# TwoPinSherlockDistribution.net
KiCad netlist of a schematic drawn in Altium Designer
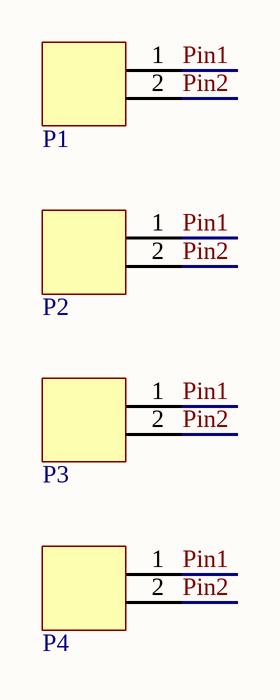
[diagram p0: TwoPinSherlockDistribution.SchDoc]

(export (version "E")
  (design (tool "Eeschema 10.0.6"))
  (components
    (comp (ref "P1")
      (value "2-pin Horz Sherlock")
      (footprint "MOLEX-HDR-1X2-SHERLOCK-HORZ")
      (fields
        (field (name "MANUFACTURER PART NUMBER") "0353630260")
        (field (name "MANUFACTURER") "Molex Inc")
      )
      (libsource (lib "SubjuGator8") (part "MOLEX-HDR-1x2-SHERLOCK_RA"))
    )
    (comp (ref "P2")
      (value "2-pin Horz Sherlock")
      (footprint "MOLEX-HDR-1X2-SHERLOCK-HORZ")
      (fields
        (field (name "MANUFACTURER PART NUMBER") "0353630260")
        (field (name "MANUFACTURER") "Molex Inc")
      )
      (libsource (lib "SubjuGator8") (part "MOLEX-HDR-1x2-SHERLOCK_RA"))
    )
    (comp (ref "P3")
      (value "2-pin Horz Sherlock")
      (footprint "MOLEX-HDR-1X2-SHERLOCK-HORZ")
      (fields
        (field (name "MANUFACTURER PART NUMBER") "0353630260")
        (field (name "MANUFACTURER") "Molex Inc")
      )
      (libsource (lib "SubjuGator8") (part "MOLEX-HDR-1x2-SHERLOCK_RA"))
    )
    (comp (ref "P4")
      (value "2-pin Horz Sherlock")
      (footprint "MOLEX-HDR-1X2-SHERLOCK-HORZ")
      (fields
        (field (name "MANUFACTURER PART NUMBER") "0353630260")
        (field (name "MANUFACTURER") "Molex Inc")
      )
      (libsource (lib "SubjuGator8") (part "MOLEX-HDR-1x2-SHERLOCK_RA"))
    )
  )
  (nets
    (net (code "1") (name "/Pin1") (class "Default")
      (node (ref "P1") (pin "1") (pinfunction "1_1") (pintype "passive"))
      (node (ref "P2") (pin "1") (pinfunction "1_1") (pintype "passive"))
      (node (ref "P3") (pin "1") (pinfunction "1_1") (pintype "passive"))
      (node (ref "P4") (pin "1") (pinfunction "1_1") (pintype "passive"))
    )
    (net (code "2") (name "/Pin2") (class "Default")
      (node (ref "P1") (pin "2") (pinfunction "2_2") (pintype "passive"))
      (node (ref "P2") (pin "2") (pinfunction "2_2") (pintype "passive"))
      (node (ref "P3") (pin "2") (pinfunction "2_2") (pintype "passive"))
      (node (ref "P4") (pin "2") (pinfunction "2_2") (pintype "passive"))
    )
  )
)
